# 1.net
KiCad netlist of a schematic drawn in Altium Designer
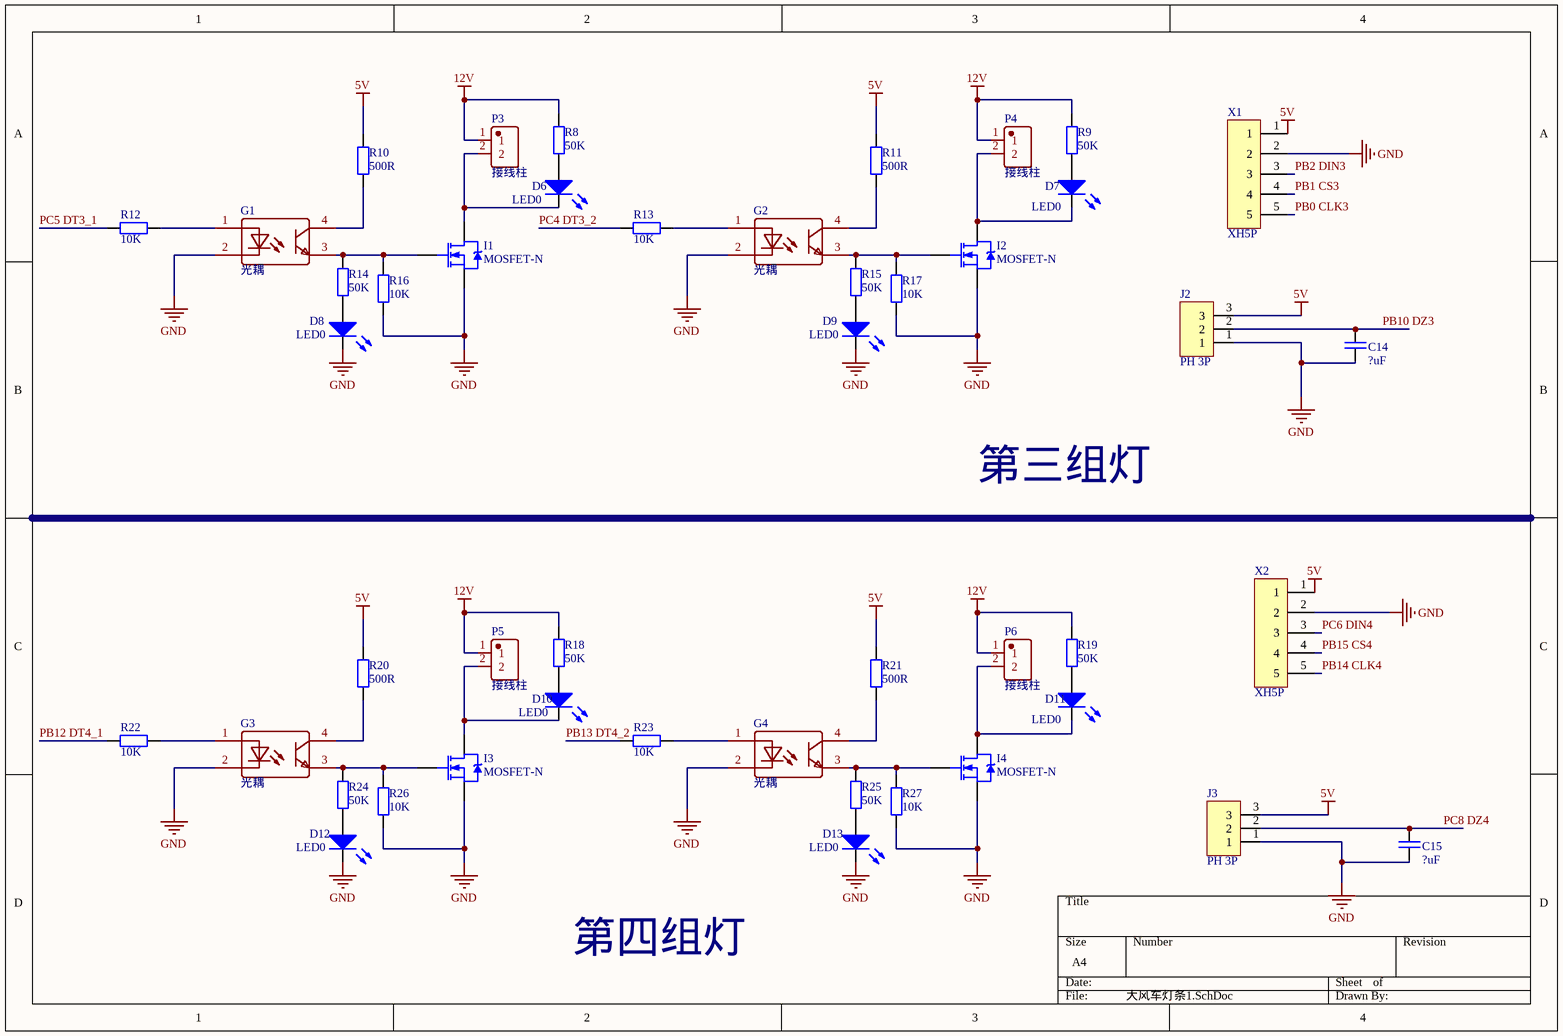
[diagram p0: 大风车灯条1.SchDoc]

(export (version "E")
  (design (tool "Eeschema 10.0.6"))
  (components
    (comp (ref "C14")
      (value "?uF")
      (footprint "0603_C")
      (fields (field (name "PUBLISHER") "Altium Limited"))
      (libsource (lib "电容-电阻-电感") (part "Cap"))
    )
    (comp (ref "C15")
      (value "?uF")
      (footprint "0603_C")
      (fields (field (name "PUBLISHER") "Altium Limited"))
      (libsource (lib "电容-电阻-电感") (part "Cap"))
    )
    (comp (ref "D6")
      (value "LED0")
      (footprint "LED-0603")
      (description "发光二极管")
      (fields (field (name "PUBLISHER") "Altium Limited"))
      (libsource (lib "二极管-晶体管") (part "LED0"))
    )
    (comp (ref "D7")
      (value "LED0")
      (footprint "LED-0603")
      (description "发光二极管")
      (fields (field (name "PUBLISHER") "Altium Limited"))
      (libsource (lib "二极管-晶体管") (part "LED0"))
    )
    (comp (ref "D8")
      (value "LED0")
      (footprint "LED-0603")
      (description "发光二极管")
      (fields (field (name "PUBLISHER") "Altium Limited"))
      (libsource (lib "二极管-晶体管") (part "LED0"))
    )
    (comp (ref "D9")
      (value "LED0")
      (footprint "LED-0603")
      (description "发光二极管")
      (fields (field (name "PUBLISHER") "Altium Limited"))
      (libsource (lib "二极管-晶体管") (part "LED0"))
    )
    (comp (ref "D10")
      (value "LED0")
      (footprint "LED-0603")
      (description "发光二极管")
      (fields (field (name "PUBLISHER") "Altium Limited"))
      (libsource (lib "二极管-晶体管") (part "LED0"))
    )
    (comp (ref "D11")
      (value "LED0")
      (footprint "LED-0603")
      (description "发光二极管")
      (fields (field (name "PUBLISHER") "Altium Limited"))
      (libsource (lib "二极管-晶体管") (part "LED0"))
    )
    (comp (ref "D12")
      (value "LED0")
      (footprint "LED-0603")
      (description "发光二极管")
      (fields (field (name "PUBLISHER") "Altium Limited"))
      (libsource (lib "二极管-晶体管") (part "LED0"))
    )
    (comp (ref "D13")
      (value "LED0")
      (footprint "LED-0603")
      (description "发光二极管")
      (fields (field (name "PUBLISHER") "Altium Limited"))
      (libsource (lib "二极管-晶体管") (part "LED0"))
    )
    (comp (ref "G1") (value "光耦") (footprint "SMD-4") (libsource (lib "大风车") (part "光耦")))
    (comp (ref "G2") (value "光耦") (footprint "SMD-4") (libsource (lib "大风车") (part "光耦")))
    (comp (ref "G3") (value "光耦") (footprint "SMD-4") (libsource (lib "大风车") (part "光耦")))
    (comp (ref "G4") (value "光耦") (footprint "SMD-4") (libsource (lib "大风车") (part "光耦")))
    (comp (ref "I1") (value "MOSFET-N") (footprint "VSONP-8") (libsource (lib "大风兄弟") (part "MOSFET-N")))
    (comp (ref "I2") (value "MOSFET-N") (footprint "VSONP-8") (libsource (lib "大风兄弟") (part "MOSFET-N")))
    (comp (ref "I3") (value "MOSFET-N") (footprint "VSONP-8") (libsource (lib "大风兄弟") (part "MOSFET-N")))
    (comp (ref "I4") (value "MOSFET-N") (footprint "VSONP-8") (libsource (lib "大风兄弟") (part "MOSFET-N")))
    (comp (ref "J2") (value "PH 3P") (footprint "PH3P") (libsource (lib "连接器") (part "PH 3P")))
    (comp (ref "J3") (value "PH 3P") (footprint "PH3P") (libsource (lib "连接器") (part "PH 3P")))
    (comp (ref "P3") (value "接线柱") (footprint "XT30-F") (libsource (lib "大风车") (part "接线柱")))
    (comp (ref "P4") (value "接线柱") (footprint "XT30-F") (libsource (lib "大风车") (part "接线柱")))
    (comp (ref "P5") (value "接线柱") (footprint "XT30-F") (libsource (lib "大风车") (part "接线柱")))
    (comp (ref "P6") (value "接线柱") (footprint "XT30-F") (libsource (lib "大风车") (part "接线柱")))
    (comp (ref "R8")
      (value "50K")
      (footprint "0603_R")
      (fields (field (name "PUBLISHER") "Altium Limited"))
      (libsource (lib "电容-电阻-电感") (part "Res"))
    )
    (comp (ref "R9")
      (value "50K")
      (footprint "0603_R")
      (fields (field (name "PUBLISHER") "Altium Limited"))
      (libsource (lib "电容-电阻-电感") (part "Res"))
    )
    (comp (ref "R10")
      (value "500R")
      (footprint "0603_R")
      (fields (field (name "PUBLISHER") "Altium Limited"))
      (libsource (lib "电容-电阻-电感") (part "Res"))
    )
    (comp (ref "R11")
      (value "500R")
      (footprint "0603_R")
      (fields (field (name "PUBLISHER") "Altium Limited"))
      (libsource (lib "电容-电阻-电感") (part "Res"))
    )
    (comp (ref "R12")
      (value "10K")
      (footprint "0603_R")
      (fields (field (name "PUBLISHER") "Altium Limited"))
      (libsource (lib "") (part "Res_1"))
    )
    (comp (ref "R13")
      (value "10K")
      (footprint "0603_R")
      (fields (field (name "PUBLISHER") "Altium Limited"))
      (libsource (lib "") (part "Res_1"))
    )
    (comp (ref "R14")
      (value "50K")
      (footprint "0603_R")
      (fields (field (name "PUBLISHER") "Altium Limited"))
      (libsource (lib "电容-电阻-电感") (part "Res"))
    )
    (comp (ref "R15")
      (value "50K")
      (footprint "0603_R")
      (fields (field (name "PUBLISHER") "Altium Limited"))
      (libsource (lib "电容-电阻-电感") (part "Res"))
    )
    (comp (ref "R16")
      (value "10K")
      (footprint "0603_R")
      (fields (field (name "PUBLISHER") "Altium Limited"))
      (libsource (lib "电容-电阻-电感") (part "Res"))
    )
    (comp (ref "R17")
      (value "10K")
      (footprint "0603_R")
      (fields (field (name "PUBLISHER") "Altium Limited"))
      (libsource (lib "电容-电阻-电感") (part "Res"))
    )
    (comp (ref "R18")
      (value "50K")
      (footprint "0603_R")
      (fields (field (name "PUBLISHER") "Altium Limited"))
      (libsource (lib "电容-电阻-电感") (part "Res"))
    )
    (comp (ref "R19")
      (value "50K")
      (footprint "0603_R")
      (fields (field (name "PUBLISHER") "Altium Limited"))
      (libsource (lib "电容-电阻-电感") (part "Res"))
    )
    (comp (ref "R20")
      (value "500R")
      (footprint "0603_R")
      (fields (field (name "PUBLISHER") "Altium Limited"))
      (libsource (lib "电容-电阻-电感") (part "Res"))
    )
    (comp (ref "R21")
      (value "500R")
      (footprint "0603_R")
      (fields (field (name "PUBLISHER") "Altium Limited"))
      (libsource (lib "电容-电阻-电感") (part "Res"))
    )
    (comp (ref "R22")
      (value "10K")
      (footprint "0603_R")
      (fields (field (name "PUBLISHER") "Altium Limited"))
      (libsource (lib "") (part "Res_1"))
    )
    (comp (ref "R23")
      (value "10K")
      (footprint "0603_R")
      (fields (field (name "PUBLISHER") "Altium Limited"))
      (libsource (lib "") (part "Res_1"))
    )
    (comp (ref "R24")
      (value "50K")
      (footprint "0603_R")
      (fields (field (name "PUBLISHER") "Altium Limited"))
      (libsource (lib "电容-电阻-电感") (part "Res"))
    )
    (comp (ref "R25")
      (value "50K")
      (footprint "0603_R")
      (fields (field (name "PUBLISHER") "Altium Limited"))
      (libsource (lib "电容-电阻-电感") (part "Res"))
    )
    (comp (ref "R26")
      (value "10K")
      (footprint "0603_R")
      (fields (field (name "PUBLISHER") "Altium Limited"))
      (libsource (lib "电容-电阻-电感") (part "Res"))
    )
    (comp (ref "R27")
      (value "10K")
      (footprint "0603_R")
      (fields (field (name "PUBLISHER") "Altium Limited"))
      (libsource (lib "电容-电阻-电感") (part "Res"))
    )
    (comp (ref "X1") (value "XH5P") (footprint "XH5P") (libsource (lib "大风车") (part "XH5P")))
    (comp (ref "X2") (value "XH5P") (footprint "XH5P") (libsource (lib "大风车") (part "XH5P")))
  )
  (nets
    (net (code "1") (name "/PB0 CLK3") (class "Default")
      (node (ref "X1") (pin "5") (pinfunction "5_5") (pintype "power_in"))
    )
    (net (code "2") (name "/PB1 CS3") (class "Default")
      (node (ref "X1") (pin "4") (pinfunction "4_4") (pintype "passive"))
    )
    (net (code "3") (name "/PB2 DIN3") (class "Default")
      (node (ref "X1") (pin "3") (pinfunction "3_3") (pintype "passive"))
    )
    (net (code "4") (name "/PB10 DZ3") (class "Default")
      (node (ref "C14") (pin "2") (pinfunction "2_2") (pintype "passive"))
      (node (ref "J2") (pin "2") (pinfunction "2_2") (pintype "power_in"))
    )
    (net (code "5") (name "/PB12 DT4_1") (class "Default")
      (node (ref "R22") (pin "1") (pinfunction "1_1") (pintype "passive"))
    )
    (net (code "6") (name "/PB13 DT4_2") (class "Default")
      (node (ref "R23") (pin "1") (pinfunction "1_1") (pintype "passive"))
    )
    (net (code "7") (name "/PB14 CLK4") (class "Default")
      (node (ref "X2") (pin "5") (pinfunction "5_5") (pintype "power_in"))
    )
    (net (code "8") (name "/PB15 CS4") (class "Default")
      (node (ref "X2") (pin "4") (pinfunction "4_4") (pintype "passive"))
    )
    (net (code "9") (name "/PC4 DT3_2") (class "Default")
      (node (ref "R13") (pin "1") (pinfunction "1_1") (pintype "passive"))
    )
    (net (code "10") (name "/PC5 DT3_1") (class "Default")
      (node (ref "R12") (pin "1") (pinfunction "1_1") (pintype "passive"))
    )
    (net (code "11") (name "/PC6 DIN4") (class "Default")
      (node (ref "X2") (pin "3") (pinfunction "3_3") (pintype "passive"))
    )
    (net (code "12") (name "/PC8 DZ4") (class "Default")
      (node (ref "C15") (pin "2") (pinfunction "2_2") (pintype "passive"))
      (node (ref "J3") (pin "2") (pinfunction "2_2") (pintype "power_in"))
    )
    (net (code "13") (name "5V") (class "Default")
      (node (ref "J2") (pin "3") (pinfunction "3_3") (pintype "power_in"))
      (node (ref "J3") (pin "3") (pinfunction "3_3") (pintype "power_in"))
      (node (ref "R10") (pin "2") (pinfunction "2_2") (pintype "passive"))
      (node (ref "R11") (pin "2") (pinfunction "2_2") (pintype "passive"))
      (node (ref "R20") (pin "2") (pinfunction "2_2") (pintype "passive"))
      (node (ref "R21") (pin "2") (pinfunction "2_2") (pintype "passive"))
      (node (ref "X1") (pin "1") (pinfunction "1_1") (pintype "passive"))
      (node (ref "X2") (pin "1") (pinfunction "1_1") (pintype "passive"))
    )
    (net (code "14") (name "12V") (class "Default")
      (node (ref "P3") (pin "1") (pinfunction "1_1") (pintype "passive"))
      (node (ref "P4") (pin "1") (pinfunction "1_1") (pintype "passive"))
      (node (ref "P5") (pin "1") (pinfunction "1_1") (pintype "passive"))
      (node (ref "P6") (pin "1") (pinfunction "1_1") (pintype "passive"))
      (node (ref "R18") (pin "2") (pinfunction "2_2") (pintype "passive"))
      (node (ref "R19") (pin "2") (pinfunction "2_2") (pintype "passive"))
      (node (ref "R8") (pin "2") (pinfunction "2_2") (pintype "passive"))
      (node (ref "R9") (pin "2") (pinfunction "2_2") (pintype "passive"))
    )
    (net (code "15") (name "GND") (class "Default")
      (node (ref "C14") (pin "1") (pinfunction "1_1") (pintype "passive"))
      (node (ref "C15") (pin "1") (pinfunction "1_1") (pintype "passive"))
      (node (ref "D12") (pin "2") (pinfunction "K_2") (pintype "passive"))
      (node (ref "D13") (pin "2") (pinfunction "K_2") (pintype "passive"))
      (node (ref "D8") (pin "2") (pinfunction "K_2") (pintype "passive"))
      (node (ref "D9") (pin "2") (pinfunction "K_2") (pintype "passive"))
      (node (ref "G1") (pin "2") (pinfunction "CAT_2") (pintype "passive"))
      (node (ref "G2") (pin "2") (pinfunction "CAT_2") (pintype "passive"))
      (node (ref "G3") (pin "2") (pinfunction "CAT_2") (pintype "passive"))
      (node (ref "G4") (pin "2") (pinfunction "CAT_2") (pintype "passive"))
      (node (ref "I1") (pin "S") (pinfunction "S_S") (pintype "passive"))
      (node (ref "I2") (pin "S") (pinfunction "S_S") (pintype "passive"))
      (node (ref "I3") (pin "S") (pinfunction "S_S") (pintype "passive"))
      (node (ref "I4") (pin "S") (pinfunction "S_S") (pintype "passive"))
      (node (ref "J2") (pin "1") (pinfunction "1_1") (pintype "power_in"))
      (node (ref "J3") (pin "1") (pinfunction "1_1") (pintype "power_in"))
      (node (ref "R16") (pin "1") (pinfunction "1_1") (pintype "passive"))
      (node (ref "R17") (pin "1") (pinfunction "1_1") (pintype "passive"))
      (node (ref "R26") (pin "1") (pinfunction "1_1") (pintype "passive"))
      (node (ref "R27") (pin "1") (pinfunction "1_1") (pintype "passive"))
      (node (ref "X1") (pin "2") (pinfunction "2_2") (pintype "passive"))
      (node (ref "X2") (pin "2") (pinfunction "2_2") (pintype "passive"))
    )
    (net (code "16") (name "Net-(D6-A)") (class "Default")
      (node (ref "D6") (pin "1") (pinfunction "A_1") (pintype "passive"))
      (node (ref "R8") (pin "1") (pinfunction "1_1") (pintype "passive"))
    )
    (net (code "17") (name "Net-(D6-K)") (class "Default")
      (node (ref "D6") (pin "2") (pinfunction "K_2") (pintype "passive"))
      (node (ref "I1") (pin "D") (pinfunction "D_D") (pintype "passive"))
      (node (ref "P3") (pin "2") (pinfunction "2_2") (pintype "passive"))
    )
    (net (code "18") (name "Net-(D7-A)") (class "Default")
      (node (ref "D7") (pin "1") (pinfunction "A_1") (pintype "passive"))
      (node (ref "R9") (pin "1") (pinfunction "1_1") (pintype "passive"))
    )
    (net (code "19") (name "Net-(D7-K)") (class "Default")
      (node (ref "D7") (pin "2") (pinfunction "K_2") (pintype "passive"))
      (node (ref "I2") (pin "D") (pinfunction "D_D") (pintype "passive"))
      (node (ref "P4") (pin "2") (pinfunction "2_2") (pintype "passive"))
    )
    (net (code "20") (name "Net-(D8-A)") (class "Default")
      (node (ref "D8") (pin "1") (pinfunction "A_1") (pintype "passive"))
      (node (ref "R14") (pin "1") (pinfunction "1_1") (pintype "passive"))
    )
    (net (code "21") (name "Net-(D9-A)") (class "Default")
      (node (ref "D9") (pin "1") (pinfunction "A_1") (pintype "passive"))
      (node (ref "R15") (pin "1") (pinfunction "1_1") (pintype "passive"))
    )
    (net (code "22") (name "Net-(D10-A)") (class "Default")
      (node (ref "D10") (pin "1") (pinfunction "A_1") (pintype "passive"))
      (node (ref "R18") (pin "1") (pinfunction "1_1") (pintype "passive"))
    )
    (net (code "23") (name "Net-(D10-K)") (class "Default")
      (node (ref "D10") (pin "2") (pinfunction "K_2") (pintype "passive"))
      (node (ref "I3") (pin "D") (pinfunction "D_D") (pintype "passive"))
      (node (ref "P5") (pin "2") (pinfunction "2_2") (pintype "passive"))
    )
    (net (code "24") (name "Net-(D11-A)") (class "Default")
      (node (ref "D11") (pin "1") (pinfunction "A_1") (pintype "passive"))
      (node (ref "R19") (pin "1") (pinfunction "1_1") (pintype "passive"))
    )
    (net (code "25") (name "Net-(D11-K)") (class "Default")
      (node (ref "D11") (pin "2") (pinfunction "K_2") (pintype "passive"))
      (node (ref "I4") (pin "D") (pinfunction "D_D") (pintype "passive"))
      (node (ref "P6") (pin "2") (pinfunction "2_2") (pintype "passive"))
    )
    (net (code "26") (name "Net-(D12-A)") (class "Default")
      (node (ref "D12") (pin "1") (pinfunction "A_1") (pintype "passive"))
      (node (ref "R24") (pin "1") (pinfunction "1_1") (pintype "passive"))
    )
    (net (code "27") (name "Net-(D13-A)") (class "Default")
      (node (ref "D13") (pin "1") (pinfunction "A_1") (pintype "passive"))
      (node (ref "R25") (pin "1") (pinfunction "1_1") (pintype "passive"))
    )
    (net (code "28") (name "Net-(G1-AN)") (class "Default")
      (node (ref "G1") (pin "1") (pinfunction "AN_1") (pintype "passive"))
      (node (ref "R12") (pin "2") (pinfunction "2_2") (pintype "passive"))
    )
    (net (code "29") (name "Net-(G1-COL)") (class "Default")
      (node (ref "G1") (pin "4") (pinfunction "COL_4") (pintype "passive"))
      (node (ref "R10") (pin "1") (pinfunction "1_1") (pintype "passive"))
    )
    (net (code "30") (name "Net-(G1-EM)") (class "Default")
      (node (ref "G1") (pin "3") (pinfunction "EM_3") (pintype "passive"))
      (node (ref "I1") (pin "G") (pinfunction "G_G") (pintype "passive"))
      (node (ref "R14") (pin "2") (pinfunction "2_2") (pintype "passive"))
      (node (ref "R16") (pin "2") (pinfunction "2_2") (pintype "passive"))
    )
    (net (code "31") (name "Net-(G2-AN)") (class "Default")
      (node (ref "G2") (pin "1") (pinfunction "AN_1") (pintype "passive"))
      (node (ref "R13") (pin "2") (pinfunction "2_2") (pintype "passive"))
    )
    (net (code "32") (name "Net-(G2-COL)") (class "Default")
      (node (ref "G2") (pin "4") (pinfunction "COL_4") (pintype "passive"))
      (node (ref "R11") (pin "1") (pinfunction "1_1") (pintype "passive"))
    )
    (net (code "33") (name "Net-(G2-EM)") (class "Default")
      (node (ref "G2") (pin "3") (pinfunction "EM_3") (pintype "passive"))
      (node (ref "I2") (pin "G") (pinfunction "G_G") (pintype "passive"))
      (node (ref "R15") (pin "2") (pinfunction "2_2") (pintype "passive"))
      (node (ref "R17") (pin "2") (pinfunction "2_2") (pintype "passive"))
    )
    (net (code "34") (name "Net-(G3-AN)") (class "Default")
      (node (ref "G3") (pin "1") (pinfunction "AN_1") (pintype "passive"))
      (node (ref "R22") (pin "2") (pinfunction "2_2") (pintype "passive"))
    )
    (net (code "35") (name "Net-(G3-COL)") (class "Default")
      (node (ref "G3") (pin "4") (pinfunction "COL_4") (pintype "passive"))
      (node (ref "R20") (pin "1") (pinfunction "1_1") (pintype "passive"))
    )
    (net (code "36") (name "Net-(G3-EM)") (class "Default")
      (node (ref "G3") (pin "3") (pinfunction "EM_3") (pintype "passive"))
      (node (ref "I3") (pin "G") (pinfunction "G_G") (pintype "passive"))
      (node (ref "R24") (pin "2") (pinfunction "2_2") (pintype "passive"))
      (node (ref "R26") (pin "2") (pinfunction "2_2") (pintype "passive"))
    )
    (net (code "37") (name "Net-(G4-AN)") (class "Default")
      (node (ref "G4") (pin "1") (pinfunction "AN_1") (pintype "passive"))
      (node (ref "R23") (pin "2") (pinfunction "2_2") (pintype "passive"))
    )
    (net (code "38") (name "Net-(G4-COL)") (class "Default")
      (node (ref "G4") (pin "4") (pinfunction "COL_4") (pintype "passive"))
      (node (ref "R21") (pin "1") (pinfunction "1_1") (pintype "passive"))
    )
    (net (code "39") (name "Net-(G4-EM)") (class "Default")
      (node (ref "G4") (pin "3") (pinfunction "EM_3") (pintype "passive"))
      (node (ref "I4") (pin "G") (pinfunction "G_G") (pintype "passive"))
      (node (ref "R25") (pin "2") (pinfunction "2_2") (pintype "passive"))
      (node (ref "R27") (pin "2") (pinfunction "2_2") (pintype "passive"))
    )
  )
)
